# HyperRail_Board_vLED.net
KiCad netlist of a schematic drawn in EAGLE
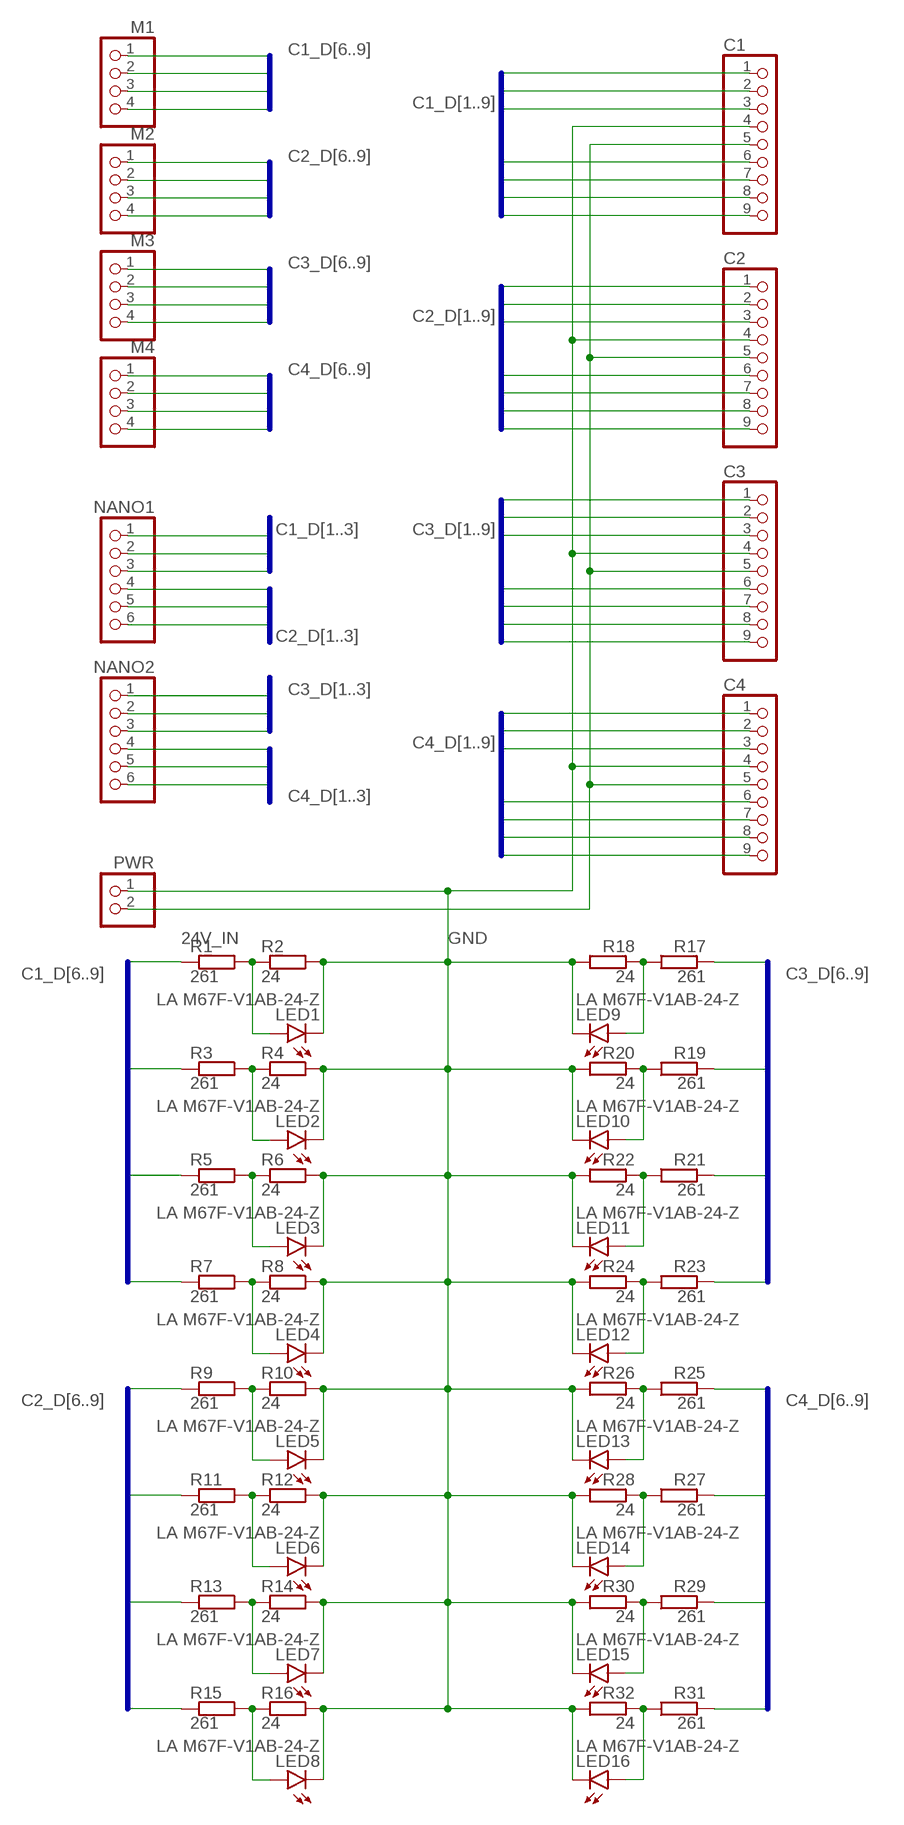
[diagram p0: schematic, sheet 1]

(export (version "E")
  (design (tool "Eeschema 10.0.6"))
  (components
    (comp (ref "C1")
      (value "PINHD-1X9")
      (footprint "eagle-import:1X09")
      (libsource (lib "eagle-import") (part "PINHD-1X9"))
    )
    (comp (ref "C2")
      (value "PINHD-1X9")
      (footprint "eagle-import:1X09")
      (libsource (lib "eagle-import") (part "PINHD-1X9"))
    )
    (comp (ref "C3")
      (value "PINHD-1X9")
      (footprint "eagle-import:1X09")
      (libsource (lib "eagle-import") (part "PINHD-1X9"))
    )
    (comp (ref "C4")
      (value "PINHD-1X9")
      (footprint "eagle-import:1X09")
      (libsource (lib "eagle-import") (part "PINHD-1X9"))
    )
    (comp (ref "LED1")
      (value "LA M67F-V1AB-24-Z")
      (footprint "eagle-import:PLCC2")
      (libsource (lib "eagle-import") (part "_T679-?-1D2E2LY"))
    )
    (comp (ref "LED2")
      (value "LA M67F-V1AB-24-Z")
      (footprint "eagle-import:PLCC2")
      (libsource (lib "eagle-import") (part "_T679-?-1D2E2LY"))
    )
    (comp (ref "LED3")
      (value "LA M67F-V1AB-24-Z")
      (footprint "eagle-import:PLCC2")
      (libsource (lib "eagle-import") (part "_T679-?-1D2E2LY"))
    )
    (comp (ref "LED4")
      (value "LA M67F-V1AB-24-Z")
      (footprint "eagle-import:PLCC2")
      (libsource (lib "eagle-import") (part "_T679-?-1D2E2LY"))
    )
    (comp (ref "LED5")
      (value "LA M67F-V1AB-24-Z")
      (footprint "eagle-import:PLCC2")
      (libsource (lib "eagle-import") (part "_T679-?-1D2E2LY"))
    )
    (comp (ref "LED6")
      (value "LA M67F-V1AB-24-Z")
      (footprint "eagle-import:PLCC2")
      (libsource (lib "eagle-import") (part "_T679-?-1D2E2LY"))
    )
    (comp (ref "LED7")
      (value "LA M67F-V1AB-24-Z")
      (footprint "eagle-import:PLCC2")
      (libsource (lib "eagle-import") (part "_T679-?-1D2E2LY"))
    )
    (comp (ref "LED8")
      (value "LA M67F-V1AB-24-Z")
      (footprint "eagle-import:PLCC2")
      (libsource (lib "eagle-import") (part "_T679-?-1D2E2LY"))
    )
    (comp (ref "LED9")
      (value "LA M67F-V1AB-24-Z")
      (footprint "eagle-import:PLCC2")
      (libsource (lib "eagle-import") (part "_T679-?-1D2E2LY"))
    )
    (comp (ref "LED10")
      (value "LA M67F-V1AB-24-Z")
      (footprint "eagle-import:PLCC2")
      (libsource (lib "eagle-import") (part "_T679-?-1D2E2LY"))
    )
    (comp (ref "LED11")
      (value "LA M67F-V1AB-24-Z")
      (footprint "eagle-import:PLCC2")
      (libsource (lib "eagle-import") (part "_T679-?-1D2E2LY"))
    )
    (comp (ref "LED12")
      (value "LA M67F-V1AB-24-Z")
      (footprint "eagle-import:PLCC2")
      (libsource (lib "eagle-import") (part "_T679-?-1D2E2LY"))
    )
    (comp (ref "LED13")
      (value "LA M67F-V1AB-24-Z")
      (footprint "eagle-import:PLCC2")
      (libsource (lib "eagle-import") (part "_T679-?-1D2E2LY"))
    )
    (comp (ref "LED14")
      (value "LA M67F-V1AB-24-Z")
      (footprint "eagle-import:PLCC2")
      (libsource (lib "eagle-import") (part "_T679-?-1D2E2LY"))
    )
    (comp (ref "LED15")
      (value "LA M67F-V1AB-24-Z")
      (footprint "eagle-import:PLCC2")
      (libsource (lib "eagle-import") (part "_T679-?-1D2E2LY"))
    )
    (comp (ref "LED16")
      (value "LA M67F-V1AB-24-Z")
      (footprint "eagle-import:PLCC2")
      (libsource (lib "eagle-import") (part "_T679-?-1D2E2LY"))
    )
    (comp (ref "M1")
      (value "PINHD-1X4")
      (footprint "eagle-import:1X04")
      (libsource (lib "eagle-import") (part "PINHD-1X4"))
    )
    (comp (ref "M2")
      (value "PINHD-1X4")
      (footprint "eagle-import:1X04")
      (libsource (lib "eagle-import") (part "PINHD-1X4"))
    )
    (comp (ref "M3")
      (value "PINHD-1X4")
      (footprint "eagle-import:1X04")
      (libsource (lib "eagle-import") (part "PINHD-1X4"))
    )
    (comp (ref "M4")
      (value "PINHD-1X4")
      (footprint "eagle-import:1X04")
      (libsource (lib "eagle-import") (part "PINHD-1X4"))
    )
    (comp (ref "NANO1")
      (value "PINHD-1X6")
      (footprint "eagle-import:1X06")
      (libsource (lib "eagle-import") (part "PINHD-1X6"))
    )
    (comp (ref "NANO2")
      (value "PINHD-1X6")
      (footprint "eagle-import:1X06")
      (libsource (lib "eagle-import") (part "PINHD-1X6"))
    )
    (comp (ref "PWR")
      (value "PINHD-1X2")
      (footprint "eagle-import:1X02")
      (libsource (lib "eagle-import") (part "PINHD-1X2"))
    )
    (comp (ref "R1")
      (value "261")
      (footprint "eagle-import:SMK")
      (libsource (lib "eagle-import") (part "SMK"))
    )
    (comp (ref "R2")
      (value "24")
      (footprint "eagle-import:SMK")
      (libsource (lib "eagle-import") (part "SMK"))
    )
    (comp (ref "R3")
      (value "261")
      (footprint "eagle-import:SMK")
      (libsource (lib "eagle-import") (part "SMK"))
    )
    (comp (ref "R4")
      (value "24")
      (footprint "eagle-import:SMK")
      (libsource (lib "eagle-import") (part "SMK"))
    )
    (comp (ref "R5")
      (value "261")
      (footprint "eagle-import:SMK")
      (libsource (lib "eagle-import") (part "SMK"))
    )
    (comp (ref "R6")
      (value "24")
      (footprint "eagle-import:SMK")
      (libsource (lib "eagle-import") (part "SMK"))
    )
    (comp (ref "R7")
      (value "261")
      (footprint "eagle-import:SMK")
      (libsource (lib "eagle-import") (part "SMK"))
    )
    (comp (ref "R8")
      (value "24")
      (footprint "eagle-import:SMK")
      (libsource (lib "eagle-import") (part "SMK"))
    )
    (comp (ref "R9")
      (value "261")
      (footprint "eagle-import:SMK")
      (libsource (lib "eagle-import") (part "SMK"))
    )
    (comp (ref "R10")
      (value "24")
      (footprint "eagle-import:SMK")
      (libsource (lib "eagle-import") (part "SMK"))
    )
    (comp (ref "R11")
      (value "261")
      (footprint "eagle-import:SMK")
      (libsource (lib "eagle-import") (part "SMK"))
    )
    (comp (ref "R12")
      (value "24")
      (footprint "eagle-import:SMK")
      (libsource (lib "eagle-import") (part "SMK"))
    )
    (comp (ref "R13")
      (value "261")
      (footprint "eagle-import:SMK")
      (libsource (lib "eagle-import") (part "SMK"))
    )
    (comp (ref "R14")
      (value "24")
      (footprint "eagle-import:SMK")
      (libsource (lib "eagle-import") (part "SMK"))
    )
    (comp (ref "R15")
      (value "261")
      (footprint "eagle-import:SMK")
      (libsource (lib "eagle-import") (part "SMK"))
    )
    (comp (ref "R16")
      (value "24")
      (footprint "eagle-import:SMK")
      (libsource (lib "eagle-import") (part "SMK"))
    )
    (comp (ref "R17")
      (value "261")
      (footprint "eagle-import:SMK")
      (libsource (lib "eagle-import") (part "SMK"))
    )
    (comp (ref "R18")
      (value "24")
      (footprint "eagle-import:SMK")
      (libsource (lib "eagle-import") (part "SMK"))
    )
    (comp (ref "R19")
      (value "261")
      (footprint "eagle-import:SMK")
      (libsource (lib "eagle-import") (part "SMK"))
    )
    (comp (ref "R20")
      (value "24")
      (footprint "eagle-import:SMK")
      (libsource (lib "eagle-import") (part "SMK"))
    )
    (comp (ref "R21")
      (value "261")
      (footprint "eagle-import:SMK")
      (libsource (lib "eagle-import") (part "SMK"))
    )
    (comp (ref "R22")
      (value "24")
      (footprint "eagle-import:SMK")
      (libsource (lib "eagle-import") (part "SMK"))
    )
    (comp (ref "R23")
      (value "261")
      (footprint "eagle-import:SMK")
      (libsource (lib "eagle-import") (part "SMK"))
    )
    (comp (ref "R24")
      (value "24")
      (footprint "eagle-import:SMK")
      (libsource (lib "eagle-import") (part "SMK"))
    )
    (comp (ref "R25")
      (value "261")
      (footprint "eagle-import:SMK")
      (libsource (lib "eagle-import") (part "SMK"))
    )
    (comp (ref "R26")
      (value "24")
      (footprint "eagle-import:SMK")
      (libsource (lib "eagle-import") (part "SMK"))
    )
    (comp (ref "R27")
      (value "261")
      (footprint "eagle-import:SMK")
      (libsource (lib "eagle-import") (part "SMK"))
    )
    (comp (ref "R28")
      (value "24")
      (footprint "eagle-import:SMK")
      (libsource (lib "eagle-import") (part "SMK"))
    )
    (comp (ref "R29")
      (value "261")
      (footprint "eagle-import:SMK")
      (libsource (lib "eagle-import") (part "SMK"))
    )
    (comp (ref "R30")
      (value "24")
      (footprint "eagle-import:SMK")
      (libsource (lib "eagle-import") (part "SMK"))
    )
    (comp (ref "R31")
      (value "261")
      (footprint "eagle-import:SMK")
      (libsource (lib "eagle-import") (part "SMK"))
    )
    (comp (ref "R32")
      (value "24")
      (footprint "eagle-import:SMK")
      (libsource (lib "eagle-import") (part "SMK"))
    )
  )
  (nets
    (net (code "9") (name "/24V_IN") (class "Default")
      (node (ref "C1") (pin "5") (pinfunction "5_5") (pintype "passive"))
      (node (ref "C2") (pin "5") (pinfunction "5_5") (pintype "passive"))
      (node (ref "C3") (pin "5") (pinfunction "5_5") (pintype "passive"))
      (node (ref "C4") (pin "5") (pinfunction "5_5") (pintype "passive"))
      (node (ref "PWR") (pin "2") (pinfunction "2_2") (pintype "passive"))
    )
    (net (code "10") (name "/C1_D1") (class "Default")
      (node (ref "C1") (pin "1") (pinfunction "1_1") (pintype "passive"))
      (node (ref "NANO1") (pin "1") (pinfunction "1_1") (pintype "passive"))
    )
    (net (code "11") (name "/C1_D2") (class "Default")
      (node (ref "C1") (pin "2") (pinfunction "2_2") (pintype "passive"))
      (node (ref "NANO1") (pin "2") (pinfunction "2_2") (pintype "passive"))
    )
    (net (code "12") (name "/C1_D3") (class "Default")
      (node (ref "C1") (pin "3") (pinfunction "3_3") (pintype "passive"))
      (node (ref "NANO1") (pin "3") (pinfunction "3_3") (pintype "passive"))
    )
    (net (code "13") (name "/C1_D6") (class "Default")
      (node (ref "C1") (pin "6") (pinfunction "6_6") (pintype "passive"))
      (node (ref "M1") (pin "1") (pinfunction "1_1") (pintype "passive"))
      (node (ref "R1") (pin "2") (pinfunction "2_2") (pintype "passive"))
    )
    (net (code "14") (name "/C1_D7") (class "Default")
      (node (ref "C1") (pin "7") (pinfunction "7_7") (pintype "passive"))
      (node (ref "M1") (pin "2") (pinfunction "2_2") (pintype "passive"))
      (node (ref "R3") (pin "2") (pinfunction "2_2") (pintype "passive"))
    )
    (net (code "15") (name "/C1_D8") (class "Default")
      (node (ref "C1") (pin "8") (pinfunction "8_8") (pintype "passive"))
      (node (ref "M1") (pin "3") (pinfunction "3_3") (pintype "passive"))
      (node (ref "R5") (pin "2") (pinfunction "2_2") (pintype "passive"))
    )
    (net (code "16") (name "/C1_D9") (class "Default")
      (node (ref "C1") (pin "9") (pinfunction "9_9") (pintype "passive"))
      (node (ref "M1") (pin "4") (pinfunction "4_4") (pintype "passive"))
      (node (ref "R7") (pin "2") (pinfunction "2_2") (pintype "passive"))
    )
    (net (code "20") (name "/C2_D1") (class "Default")
      (node (ref "C2") (pin "1") (pinfunction "1_1") (pintype "passive"))
      (node (ref "NANO1") (pin "4") (pinfunction "4_4") (pintype "passive"))
    )
    (net (code "21") (name "/C2_D2") (class "Default")
      (node (ref "C2") (pin "2") (pinfunction "2_2") (pintype "passive"))
      (node (ref "NANO1") (pin "5") (pinfunction "5_5") (pintype "passive"))
    )
    (net (code "22") (name "/C2_D3") (class "Default")
      (node (ref "C2") (pin "3") (pinfunction "3_3") (pintype "passive"))
      (node (ref "NANO1") (pin "6") (pinfunction "6_6") (pintype "passive"))
    )
    (net (code "23") (name "/C2_D6") (class "Default")
      (node (ref "C2") (pin "6") (pinfunction "6_6") (pintype "passive"))
      (node (ref "M2") (pin "1") (pinfunction "1_1") (pintype "passive"))
      (node (ref "R9") (pin "2") (pinfunction "2_2") (pintype "passive"))
    )
    (net (code "24") (name "/C2_D7") (class "Default")
      (node (ref "C2") (pin "7") (pinfunction "7_7") (pintype "passive"))
      (node (ref "M2") (pin "2") (pinfunction "2_2") (pintype "passive"))
      (node (ref "R11") (pin "2") (pinfunction "2_2") (pintype "passive"))
    )
    (net (code "25") (name "/C2_D8") (class "Default")
      (node (ref "C2") (pin "8") (pinfunction "8_8") (pintype "passive"))
      (node (ref "M2") (pin "3") (pinfunction "3_3") (pintype "passive"))
      (node (ref "R13") (pin "2") (pinfunction "2_2") (pintype "passive"))
    )
    (net (code "26") (name "/C2_D9") (class "Default")
      (node (ref "C2") (pin "9") (pinfunction "9_9") (pintype "passive"))
      (node (ref "M2") (pin "4") (pinfunction "4_4") (pintype "passive"))
      (node (ref "R15") (pin "2") (pinfunction "2_2") (pintype "passive"))
    )
    (net (code "30") (name "/C3_D1") (class "Default")
      (node (ref "C3") (pin "1") (pinfunction "1_1") (pintype "passive"))
      (node (ref "NANO2") (pin "1") (pinfunction "1_1") (pintype "passive"))
    )
    (net (code "31") (name "/C3_D2") (class "Default")
      (node (ref "C3") (pin "2") (pinfunction "2_2") (pintype "passive"))
      (node (ref "NANO2") (pin "2") (pinfunction "2_2") (pintype "passive"))
    )
    (net (code "32") (name "/C3_D3") (class "Default")
      (node (ref "C3") (pin "3") (pinfunction "3_3") (pintype "passive"))
      (node (ref "NANO2") (pin "3") (pinfunction "3_3") (pintype "passive"))
    )
    (net (code "33") (name "/C3_D6") (class "Default")
      (node (ref "C3") (pin "6") (pinfunction "6_6") (pintype "passive"))
      (node (ref "M3") (pin "1") (pinfunction "1_1") (pintype "passive"))
      (node (ref "R17") (pin "2") (pinfunction "2_2") (pintype "passive"))
    )
    (net (code "34") (name "/C3_D7") (class "Default")
      (node (ref "C3") (pin "7") (pinfunction "7_7") (pintype "passive"))
      (node (ref "M3") (pin "2") (pinfunction "2_2") (pintype "passive"))
      (node (ref "R19") (pin "2") (pinfunction "2_2") (pintype "passive"))
    )
    (net (code "35") (name "/C3_D8") (class "Default")
      (node (ref "C3") (pin "8") (pinfunction "8_8") (pintype "passive"))
      (node (ref "M3") (pin "3") (pinfunction "3_3") (pintype "passive"))
      (node (ref "R21") (pin "2") (pinfunction "2_2") (pintype "passive"))
    )
    (net (code "36") (name "/C3_D9") (class "Default")
      (node (ref "C3") (pin "9") (pinfunction "9_9") (pintype "passive"))
      (node (ref "M3") (pin "4") (pinfunction "4_4") (pintype "passive"))
      (node (ref "R23") (pin "2") (pinfunction "2_2") (pintype "passive"))
    )
    (net (code "40") (name "/C4_D1") (class "Default")
      (node (ref "C4") (pin "1") (pinfunction "1_1") (pintype "passive"))
      (node (ref "NANO2") (pin "4") (pinfunction "4_4") (pintype "passive"))
    )
    (net (code "41") (name "/C4_D2") (class "Default")
      (node (ref "C4") (pin "2") (pinfunction "2_2") (pintype "passive"))
      (node (ref "NANO2") (pin "5") (pinfunction "5_5") (pintype "passive"))
    )
    (net (code "42") (name "/C4_D3") (class "Default")
      (node (ref "C4") (pin "3") (pinfunction "3_3") (pintype "passive"))
      (node (ref "NANO2") (pin "6") (pinfunction "6_6") (pintype "passive"))
    )
    (net (code "43") (name "/C4_D6") (class "Default")
      (node (ref "C4") (pin "6") (pinfunction "6_6") (pintype "passive"))
      (node (ref "M4") (pin "1") (pinfunction "1_1") (pintype "passive"))
      (node (ref "R25") (pin "2") (pinfunction "2_2") (pintype "passive"))
    )
    (net (code "44") (name "/C4_D7") (class "Default")
      (node (ref "C4") (pin "7") (pinfunction "7_7") (pintype "passive"))
      (node (ref "M4") (pin "2") (pinfunction "2_2") (pintype "passive"))
      (node (ref "R27") (pin "2") (pinfunction "2_2") (pintype "passive"))
    )
    (net (code "45") (name "/C4_D8") (class "Default")
      (node (ref "C4") (pin "8") (pinfunction "8_8") (pintype "passive"))
      (node (ref "M4") (pin "3") (pinfunction "3_3") (pintype "passive"))
      (node (ref "R29") (pin "2") (pinfunction "2_2") (pintype "passive"))
    )
    (net (code "46") (name "/C4_D9") (class "Default")
      (node (ref "C4") (pin "9") (pinfunction "9_9") (pintype "passive"))
      (node (ref "M4") (pin "4") (pinfunction "4_4") (pintype "passive"))
      (node (ref "R31") (pin "2") (pinfunction "2_2") (pintype "passive"))
    )
    (net (code "50") (name "/GND") (class "Default")
      (node (ref "C1") (pin "4") (pinfunction "4_4") (pintype "passive"))
      (node (ref "C2") (pin "4") (pinfunction "4_4") (pintype "passive"))
      (node (ref "C3") (pin "4") (pinfunction "4_4") (pintype "passive"))
      (node (ref "C4") (pin "4") (pinfunction "4_4") (pintype "passive"))
      (node (ref "LED1") (pin "C") (pinfunction "C_C") (pintype "passive"))
      (node (ref "LED10") (pin "C") (pinfunction "C_C") (pintype "passive"))
      (node (ref "LED11") (pin "C") (pinfunction "C_C") (pintype "passive"))
      (node (ref "LED12") (pin "C") (pinfunction "C_C") (pintype "passive"))
      (node (ref "LED13") (pin "C") (pinfunction "C_C") (pintype "passive"))
      (node (ref "LED14") (pin "C") (pinfunction "C_C") (pintype "passive"))
      (node (ref "LED15") (pin "C") (pinfunction "C_C") (pintype "passive"))
      (node (ref "LED16") (pin "C") (pinfunction "C_C") (pintype "passive"))
      (node (ref "LED2") (pin "C") (pinfunction "C_C") (pintype "passive"))
      (node (ref "LED3") (pin "C") (pinfunction "C_C") (pintype "passive"))
      (node (ref "LED4") (pin "C") (pinfunction "C_C") (pintype "passive"))
      (node (ref "LED5") (pin "C") (pinfunction "C_C") (pintype "passive"))
      (node (ref "LED6") (pin "C") (pinfunction "C_C") (pintype "passive"))
      (node (ref "LED7") (pin "C") (pinfunction "C_C") (pintype "passive"))
      (node (ref "LED8") (pin "C") (pinfunction "C_C") (pintype "passive"))
      (node (ref "LED9") (pin "C") (pinfunction "C_C") (pintype "passive"))
      (node (ref "PWR") (pin "1") (pinfunction "1_1") (pintype "passive"))
      (node (ref "R10") (pin "1") (pinfunction "1_1") (pintype "passive"))
      (node (ref "R12") (pin "1") (pinfunction "1_1") (pintype "passive"))
      (node (ref "R14") (pin "1") (pinfunction "1_1") (pintype "passive"))
      (node (ref "R16") (pin "1") (pinfunction "1_1") (pintype "passive"))
      (node (ref "R18") (pin "1") (pinfunction "1_1") (pintype "passive"))
      (node (ref "R2") (pin "1") (pinfunction "1_1") (pintype "passive"))
      (node (ref "R20") (pin "1") (pinfunction "1_1") (pintype "passive"))
      (node (ref "R22") (pin "1") (pinfunction "1_1") (pintype "passive"))
      (node (ref "R24") (pin "1") (pinfunction "1_1") (pintype "passive"))
      (node (ref "R26") (pin "1") (pinfunction "1_1") (pintype "passive"))
      (node (ref "R28") (pin "1") (pinfunction "1_1") (pintype "passive"))
      (node (ref "R30") (pin "1") (pinfunction "1_1") (pintype "passive"))
      (node (ref "R32") (pin "1") (pinfunction "1_1") (pintype "passive"))
      (node (ref "R4") (pin "1") (pinfunction "1_1") (pintype "passive"))
      (node (ref "R6") (pin "1") (pinfunction "1_1") (pintype "passive"))
      (node (ref "R8") (pin "1") (pinfunction "1_1") (pintype "passive"))
    )
    (net (code "51") (name "Net-(LED1-PadA)") (class "Default")
      (node (ref "LED1") (pin "A") (pinfunction "A_A") (pintype "passive"))
      (node (ref "R1") (pin "1") (pinfunction "1_1") (pintype "passive"))
      (node (ref "R2") (pin "2") (pinfunction "2_2") (pintype "passive"))
    )
    (net (code "52") (name "Net-(LED2-PadA)") (class "Default")
      (node (ref "LED2") (pin "A") (pinfunction "A_A") (pintype "passive"))
      (node (ref "R3") (pin "1") (pinfunction "1_1") (pintype "passive"))
      (node (ref "R4") (pin "2") (pinfunction "2_2") (pintype "passive"))
    )
    (net (code "53") (name "Net-(LED3-PadA)") (class "Default")
      (node (ref "LED3") (pin "A") (pinfunction "A_A") (pintype "passive"))
      (node (ref "R5") (pin "1") (pinfunction "1_1") (pintype "passive"))
      (node (ref "R6") (pin "2") (pinfunction "2_2") (pintype "passive"))
    )
    (net (code "54") (name "Net-(LED4-PadA)") (class "Default")
      (node (ref "LED4") (pin "A") (pinfunction "A_A") (pintype "passive"))
      (node (ref "R7") (pin "1") (pinfunction "1_1") (pintype "passive"))
      (node (ref "R8") (pin "2") (pinfunction "2_2") (pintype "passive"))
    )
    (net (code "55") (name "Net-(LED5-PadA)") (class "Default")
      (node (ref "LED5") (pin "A") (pinfunction "A_A") (pintype "passive"))
      (node (ref "R10") (pin "2") (pinfunction "2_2") (pintype "passive"))
      (node (ref "R9") (pin "1") (pinfunction "1_1") (pintype "passive"))
    )
    (net (code "56") (name "Net-(LED6-PadA)") (class "Default")
      (node (ref "LED6") (pin "A") (pinfunction "A_A") (pintype "passive"))
      (node (ref "R11") (pin "1") (pinfunction "1_1") (pintype "passive"))
      (node (ref "R12") (pin "2") (pinfunction "2_2") (pintype "passive"))
    )
    (net (code "57") (name "Net-(LED7-PadA)") (class "Default")
      (node (ref "LED7") (pin "A") (pinfunction "A_A") (pintype "passive"))
      (node (ref "R13") (pin "1") (pinfunction "1_1") (pintype "passive"))
      (node (ref "R14") (pin "2") (pinfunction "2_2") (pintype "passive"))
    )
    (net (code "58") (name "Net-(LED8-PadA)") (class "Default")
      (node (ref "LED8") (pin "A") (pinfunction "A_A") (pintype "passive"))
      (node (ref "R15") (pin "1") (pinfunction "1_1") (pintype "passive"))
      (node (ref "R16") (pin "2") (pinfunction "2_2") (pintype "passive"))
    )
    (net (code "59") (name "Net-(LED9-PadA)") (class "Default")
      (node (ref "LED9") (pin "A") (pinfunction "A_A") (pintype "passive"))
      (node (ref "R17") (pin "1") (pinfunction "1_1") (pintype "passive"))
      (node (ref "R18") (pin "2") (pinfunction "2_2") (pintype "passive"))
    )
    (net (code "60") (name "Net-(LED10-PadA)") (class "Default")
      (node (ref "LED10") (pin "A") (pinfunction "A_A") (pintype "passive"))
      (node (ref "R19") (pin "1") (pinfunction "1_1") (pintype "passive"))
      (node (ref "R20") (pin "2") (pinfunction "2_2") (pintype "passive"))
    )
    (net (code "61") (name "Net-(LED11-PadA)") (class "Default")
      (node (ref "LED11") (pin "A") (pinfunction "A_A") (pintype "passive"))
      (node (ref "R21") (pin "1") (pinfunction "1_1") (pintype "passive"))
      (node (ref "R22") (pin "2") (pinfunction "2_2") (pintype "passive"))
    )
    (net (code "62") (name "Net-(LED12-PadA)") (class "Default")
      (node (ref "LED12") (pin "A") (pinfunction "A_A") (pintype "passive"))
      (node (ref "R23") (pin "1") (pinfunction "1_1") (pintype "passive"))
      (node (ref "R24") (pin "2") (pinfunction "2_2") (pintype "passive"))
    )
    (net (code "63") (name "Net-(LED13-PadA)") (class "Default")
      (node (ref "LED13") (pin "A") (pinfunction "A_A") (pintype "passive"))
      (node (ref "R25") (pin "1") (pinfunction "1_1") (pintype "passive"))
      (node (ref "R26") (pin "2") (pinfunction "2_2") (pintype "passive"))
    )
    (net (code "64") (name "Net-(LED14-PadA)") (class "Default")
      (node (ref "LED14") (pin "A") (pinfunction "A_A") (pintype "passive"))
      (node (ref "R27") (pin "1") (pinfunction "1_1") (pintype "passive"))
      (node (ref "R28") (pin "2") (pinfunction "2_2") (pintype "passive"))
    )
    (net (code "65") (name "Net-(LED15-PadA)") (class "Default")
      (node (ref "LED15") (pin "A") (pinfunction "A_A") (pintype "passive"))
      (node (ref "R29") (pin "1") (pinfunction "1_1") (pintype "passive"))
      (node (ref "R30") (pin "2") (pinfunction "2_2") (pintype "passive"))
    )
    (net (code "66") (name "Net-(LED16-PadA)") (class "Default")
      (node (ref "LED16") (pin "A") (pinfunction "A_A") (pintype "passive"))
      (node (ref "R31") (pin "1") (pinfunction "1_1") (pintype "passive"))
      (node (ref "R32") (pin "2") (pinfunction "2_2") (pintype "passive"))
    )
  )
)
